# RouteurPV2107d.net
KiCad netlist of a schematic drawn in EAGLE
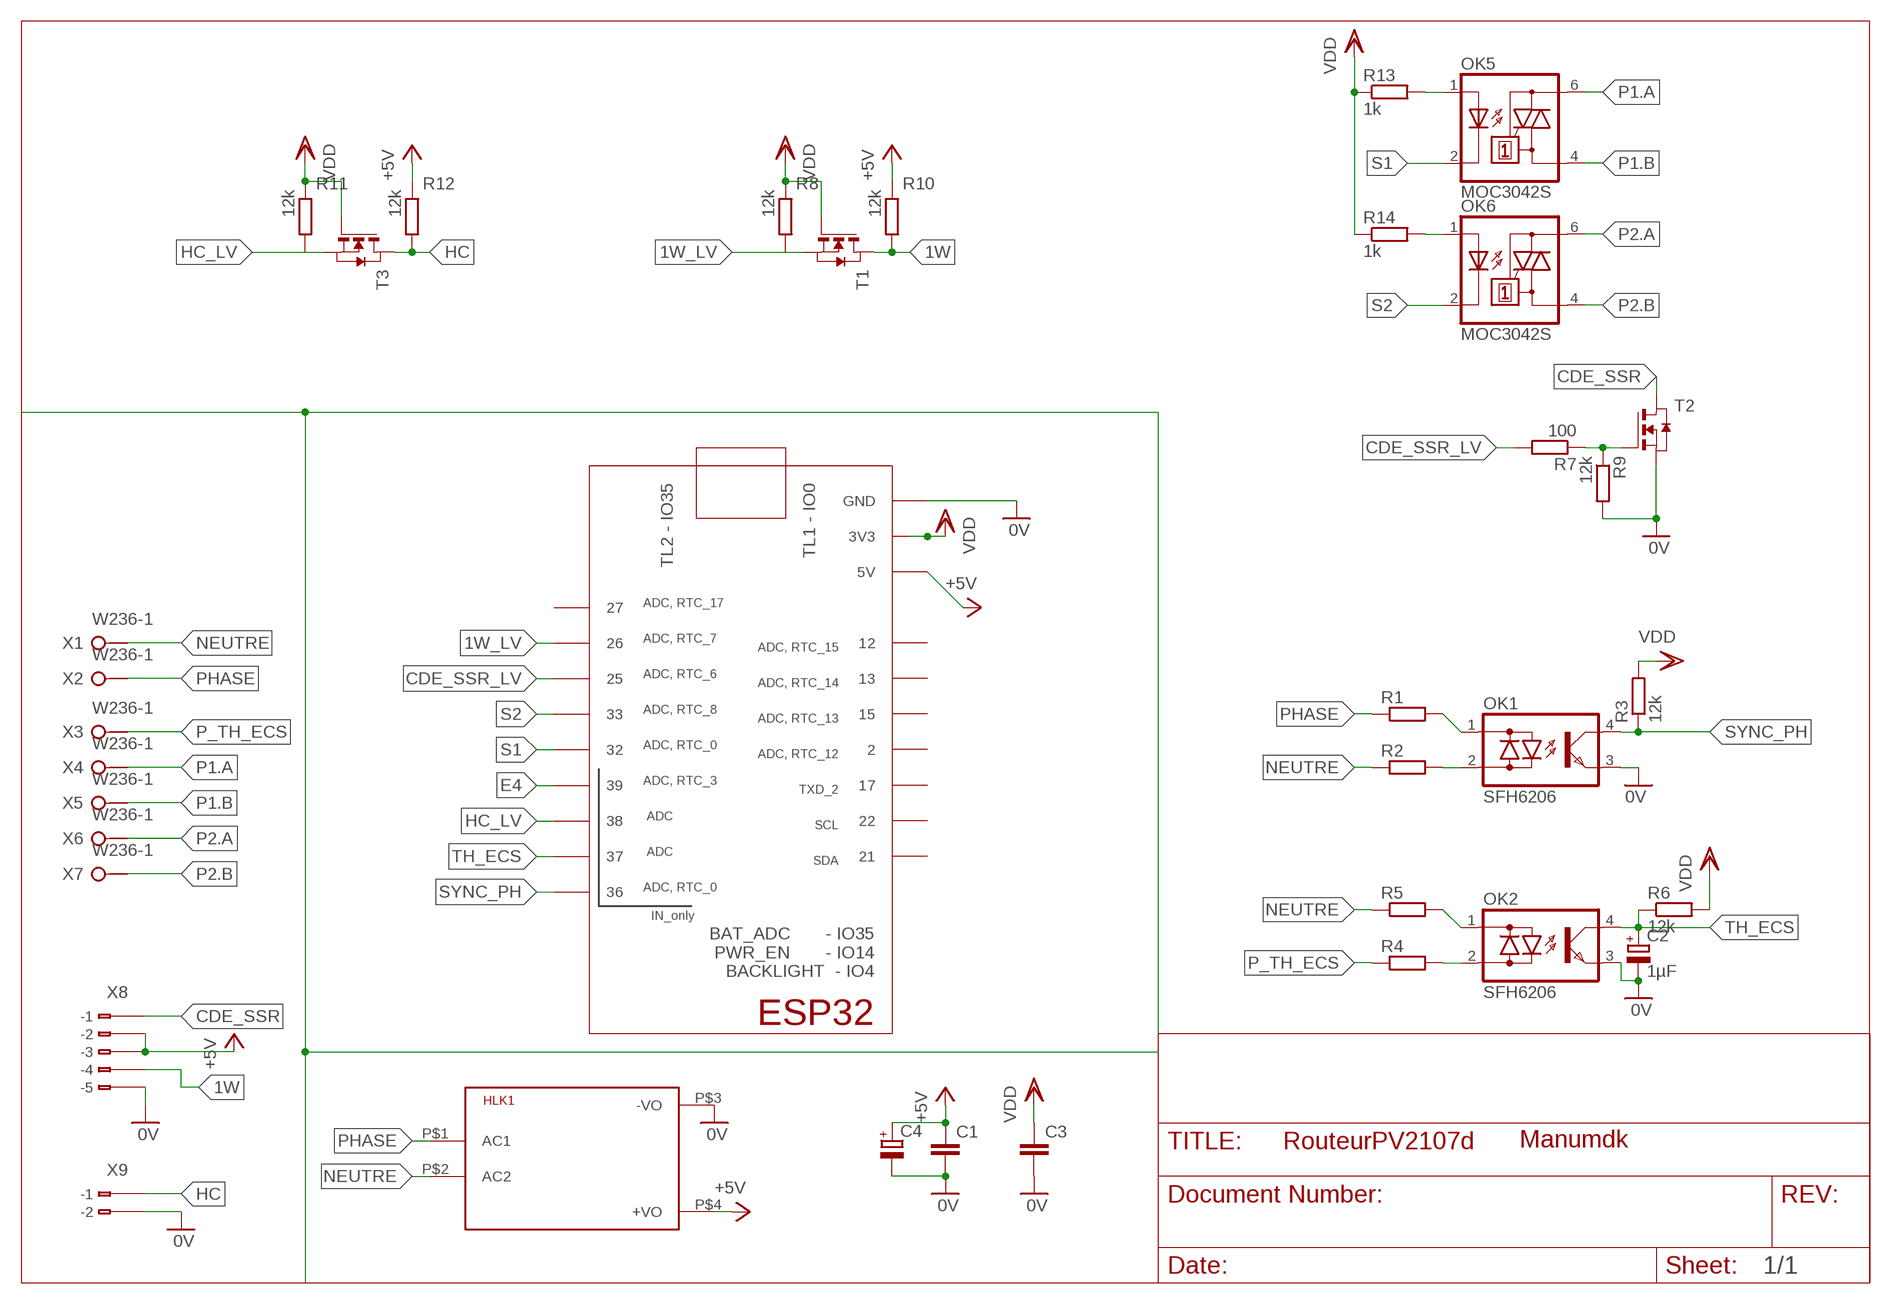
[diagram p0: schematic, sheet 1]

(export (version "E")
  (design (tool "Eeschema 10.0.6"))
  (components
    (comp (ref "C1")
      (value "C-EUC1206")
      (footprint "eagle-import:C1206")
      (libsource (lib "eagle-import") (part "C-EUC1206"))
    )
    (comp (ref "C2")
      (value "1µF")
      (footprint "eagle-import:R_2012-12R")
      (libsource (lib "eagle-import") (part "CPOL-EUR/2012-12R"))
    )
    (comp (ref "C3")
      (value "C-EUC1206")
      (footprint "eagle-import:C1206")
      (libsource (lib "eagle-import") (part "C-EUC1206"))
    )
    (comp (ref "C4")
      (value "CPOL-EUSMCC")
      (footprint "eagle-import:SMC_C")
      (libsource (lib "eagle-import") (part "CPOL-EUSMCC"))
    )
    (comp (ref "HLK1")
      (value "HLK-PM013W")
      (footprint "eagle-import:HLK-PM01")
      (libsource (lib "eagle-import") (part "HLK-PM013W"))
    )
    (comp (ref "IC1")
      (value "TTGO_DISP")
      (footprint "eagle-import:TTGO_DISP_DEFAULT")
      (libsource (lib "eagle-import") (part "TTGO_DISP"))
    )
    (comp (ref "OK1")
      (value "SFH6206")
      (footprint "eagle-import:DIL4-SMD")
      (fields (field (name "MF") "VISHAY/TELEFUNKEN") (field (name "MPN") "SFH6206-3"))
      (libsource (lib "eagle-import") (part "SFH6206"))
    )
    (comp (ref "OK2")
      (value "SFH6206")
      (footprint "eagle-import:DIL4-SMD")
      (fields (field (name "MF") "VISHAY/TELEFUNKEN") (field (name "MPN") "SFH6206-3"))
      (libsource (lib "eagle-import") (part "SFH6206"))
    )
    (comp (ref "OK5")
      (value "MOC3042S")
      (footprint "eagle-import:DIL6-SMD")
      (fields (field (name "MF") "FAIRCHILD SEMICONDUCTOR") (field (name "MPN") "MOC3042SM"))
      (libsource (lib "eagle-import") (part "MOC30S42"))
    )
    (comp (ref "OK6")
      (value "MOC3042S")
      (footprint "eagle-import:DIL6-SMD")
      (fields (field (name "MF") "FAIRCHILD SEMICONDUCTOR") (field (name "MPN") "MOC3042SM"))
      (libsource (lib "eagle-import") (part "MOC30S42"))
    )
    (comp (ref "R1")
      (value "R-EU_R2512")
      (footprint "eagle-import:R2512")
      (libsource (lib "eagle-import") (part "R-EU_R2512"))
    )
    (comp (ref "R2")
      (value "R-EU_R2512")
      (footprint "eagle-import:R2512")
      (libsource (lib "eagle-import") (part "R-EU_R2512"))
    )
    (comp (ref "R3")
      (value "12k")
      (footprint "eagle-import:R1206")
      (libsource (lib "eagle-import") (part "R-EU_R1206"))
    )
    (comp (ref "R4")
      (value "R-EU_R2512")
      (footprint "eagle-import:R2512")
      (libsource (lib "eagle-import") (part "R-EU_R2512"))
    )
    (comp (ref "R5")
      (value "R-EU_R2512")
      (footprint "eagle-import:R2512")
      (libsource (lib "eagle-import") (part "R-EU_R2512"))
    )
    (comp (ref "R6")
      (value "12k")
      (footprint "eagle-import:R1206")
      (libsource (lib "eagle-import") (part "R-EU_R1206"))
    )
    (comp (ref "R7")
      (value "100")
      (footprint "eagle-import:R1206")
      (libsource (lib "eagle-import") (part "R-EU_R1206"))
    )
    (comp (ref "R8")
      (value "12k")
      (footprint "eagle-import:R1206")
      (libsource (lib "eagle-import") (part "R-EU_R1206"))
    )
    (comp (ref "R9")
      (value "12k")
      (footprint "eagle-import:R1206")
      (libsource (lib "eagle-import") (part "R-EU_R1206"))
    )
    (comp (ref "R10")
      (value "12k")
      (footprint "eagle-import:R1206")
      (libsource (lib "eagle-import") (part "R-EU_R1206"))
    )
    (comp (ref "R11")
      (value "12k")
      (footprint "eagle-import:R1206")
      (libsource (lib "eagle-import") (part "R-EU_R1206"))
    )
    (comp (ref "R12")
      (value "12k")
      (footprint "eagle-import:R1206")
      (libsource (lib "eagle-import") (part "R-EU_R1206"))
    )
    (comp (ref "R13")
      (value "1k")
      (footprint "eagle-import:R1206")
      (libsource (lib "eagle-import") (part "R-EU_R1206"))
    )
    (comp (ref "R14")
      (value "1k")
      (footprint "eagle-import:R1206")
      (libsource (lib "eagle-import") (part "R-EU_R1206"))
    )
    (comp (ref "T1")
      (value "NMOSSOT23")
      (footprint "eagle-import:SOT-23")
      (libsource (lib "eagle-import") (part "NMOSSOT23"))
    )
    (comp (ref "T2")
      (value "NMOSSOT23")
      (footprint "eagle-import:SOT-23")
      (libsource (lib "eagle-import") (part "NMOSSOT23"))
    )
    (comp (ref "T3")
      (value "NMOSSOT23")
      (footprint "eagle-import:SOT-23")
      (libsource (lib "eagle-import") (part "NMOSSOT23"))
    )
    (comp (ref "X1")
      (value "W236-1")
      (footprint "eagle-import:W236-1")
      (libsource (lib "eagle-import") (part "W236-1"))
    )
    (comp (ref "X2")
      (value "W236-1")
      (footprint "eagle-import:W236-1")
      (libsource (lib "eagle-import") (part "W236-1"))
    )
    (comp (ref "X3")
      (value "W236-1")
      (footprint "eagle-import:W236-1")
      (libsource (lib "eagle-import") (part "W236-1"))
    )
    (comp (ref "X4")
      (value "W236-1")
      (footprint "eagle-import:W236-1")
      (libsource (lib "eagle-import") (part "W236-1"))
    )
    (comp (ref "X5")
      (value "W236-1")
      (footprint "eagle-import:W236-1")
      (libsource (lib "eagle-import") (part "W236-1"))
    )
    (comp (ref "X6")
      (value "W236-1")
      (footprint "eagle-import:W236-1")
      (libsource (lib "eagle-import") (part "W236-1"))
    )
    (comp (ref "X7")
      (value "W236-1")
      (footprint "eagle-import:W236-1")
      (libsource (lib "eagle-import") (part "W236-1"))
    )
    (comp (ref "X8")
      (value "233-505")
      (footprint "eagle-import:233-505")
      (fields (field (name "MF") "Wago Corporation") (field (name "MPN") "0233-0505"))
      (libsource (lib "eagle-import") (part "233-505"))
    )
    (comp (ref "X9")
      (value "233-102")
      (footprint "eagle-import:233-102")
      (libsource (lib "eagle-import") (part "233-102"))
    )
  )
  (nets
    (net (code "1") (name "+5V") (class "Default")
      (node (ref "C1") (pin "1") (pinfunction "1_1") (pintype "passive"))
      (node (ref "C4") (pin "+") (pinfunction "+_+") (pintype "passive"))
      (node (ref "HLK1") (pin "P$4") (pinfunction "+VO_P$4") (pintype "bidirectional"))
      (node (ref "IC1") (pin "5V") (pinfunction "5V_5V") (pintype "bidirectional"))
      (node (ref "R10") (pin "1") (pinfunction "1_1") (pintype "passive"))
      (node (ref "R12") (pin "1") (pinfunction "1_1") (pintype "passive"))
      (node (ref "X8") (pin "B2") (pinfunction "B-2_B2") (pintype "passive"))
      (node (ref "X8") (pin "B3") (pinfunction "B-3_B3") (pintype "passive"))
    )
    (net (code "2") (name "0V") (class "Default")
      (node (ref "C1") (pin "2") (pinfunction "2_2") (pintype "passive"))
      (node (ref "C2") (pin "-") (pinfunction "-_-") (pintype "passive"))
      (node (ref "C3") (pin "2") (pinfunction "2_2") (pintype "passive"))
      (node (ref "C4") (pin "-") (pinfunction "-_-") (pintype "passive"))
      (node (ref "HLK1") (pin "P$3") (pinfunction "-VO_P$3") (pintype "bidirectional"))
      (node (ref "IC1") (pin "GND_1") (pinfunction "GND_GND_1") (pintype "bidirectional"))
      (node (ref "IC1") (pin "GND_2") (pinfunction "GND_GND_2") (pintype "bidirectional"))
      (node (ref "IC1") (pin "GND_3") (pinfunction "GND_GND_3") (pintype "bidirectional"))
      (node (ref "IC1") (pin "GND_4") (pinfunction "GND_GND_4") (pintype "bidirectional"))
      (node (ref "IC1") (pin "GND_5") (pinfunction "GND_GND_5") (pintype "bidirectional"))
      (node (ref "OK1") (pin "3") (pinfunction "E_3") (pintype "passive"))
      (node (ref "OK2") (pin "3") (pinfunction "E_3") (pintype "passive"))
      (node (ref "R9") (pin "2") (pinfunction "2_2") (pintype "passive"))
      (node (ref "T2") (pin "2") (pinfunction "S_2") (pintype "passive"))
      (node (ref "X8") (pin "B5") (pinfunction "B-5_B5") (pintype "passive"))
      (node (ref "X9") (pin "B2") (pinfunction "B-2_B2") (pintype "passive"))
    )
    (net (code "3") (name "1W") (class "Default")
      (node (ref "R10") (pin "2") (pinfunction "2_2") (pintype "passive"))
      (node (ref "T1") (pin "1") (pinfunction "D_1") (pintype "passive"))
      (node (ref "X8") (pin "B4") (pinfunction "B-4_B4") (pintype "passive"))
    )
    (net (code "4") (name "1W_LV") (class "Default")
      (node (ref "IC1") (pin "26") (pinfunction "26_26") (pintype "bidirectional"))
      (node (ref "R8") (pin "2") (pinfunction "2_2") (pintype "passive"))
      (node (ref "T1") (pin "2") (pinfunction "S_2") (pintype "passive"))
    )
    (net (code "5") (name "CDE_SSR") (class "Default")
      (node (ref "T2") (pin "1") (pinfunction "D_1") (pintype "passive"))
      (node (ref "X8") (pin "B1") (pinfunction "B-1_B1") (pintype "passive"))
    )
    (net (code "6") (name "CDE_SSR_LV") (class "Default")
      (node (ref "IC1") (pin "25") (pinfunction "25_25") (pintype "bidirectional"))
      (node (ref "R7") (pin "2") (pinfunction "2_2") (pintype "passive"))
    )
    (net (code "7") (name "E4") (class "Default")
      (node (ref "IC1") (pin "39") (pinfunction "39_39") (pintype "bidirectional"))
    )
    (net (code "8") (name "HC") (class "Default")
      (node (ref "R12") (pin "2") (pinfunction "2_2") (pintype "passive"))
      (node (ref "T3") (pin "1") (pinfunction "D_1") (pintype "passive"))
      (node (ref "X9") (pin "B1") (pinfunction "B-1_B1") (pintype "passive"))
    )
    (net (code "9") (name "HC_LV") (class "Default")
      (node (ref "IC1") (pin "38") (pinfunction "38_38") (pintype "bidirectional"))
      (node (ref "R11") (pin "2") (pinfunction "2_2") (pintype "passive"))
      (node (ref "T3") (pin "2") (pinfunction "S_2") (pintype "passive"))
    )
    (net (code "10") (name "NEUTRE") (class "Default")
      (node (ref "HLK1") (pin "P$2") (pinfunction "AC2_P$2") (pintype "bidirectional"))
      (node (ref "R2") (pin "1") (pinfunction "1_1") (pintype "passive"))
      (node (ref "R5") (pin "1") (pinfunction "1_1") (pintype "passive"))
      (node (ref "X1") (pin "1") (pinfunction "KL1_1") (pintype "passive"))
    )
    (net (code "11") (name "Net-(OK1-AC1)") (class "Default")
      (node (ref "OK1") (pin "1") (pinfunction "AC1_1") (pintype "passive"))
      (node (ref "R1") (pin "2") (pinfunction "2_2") (pintype "passive"))
    )
    (net (code "12") (name "Net-(OK1-AC2)") (class "Default")
      (node (ref "OK1") (pin "2") (pinfunction "AC2_2") (pintype "passive"))
      (node (ref "R2") (pin "2") (pinfunction "2_2") (pintype "passive"))
    )
    (net (code "13") (name "Net-(OK2-AC1)") (class "Default")
      (node (ref "OK2") (pin "1") (pinfunction "AC1_1") (pintype "passive"))
      (node (ref "R5") (pin "2") (pinfunction "2_2") (pintype "passive"))
    )
    (net (code "14") (name "Net-(OK2-AC2)") (class "Default")
      (node (ref "OK2") (pin "2") (pinfunction "AC2_2") (pintype "passive"))
      (node (ref "R4") (pin "2") (pinfunction "2_2") (pintype "passive"))
    )
    (net (code "15") (name "Net-(OK5-A)") (class "Default")
      (node (ref "OK5") (pin "1") (pinfunction "A_1") (pintype "passive"))
      (node (ref "R13") (pin "2") (pinfunction "2_2") (pintype "passive"))
    )
    (net (code "16") (name "Net-(OK6-A)") (class "Default")
      (node (ref "OK6") (pin "1") (pinfunction "A_1") (pintype "passive"))
      (node (ref "R14") (pin "2") (pinfunction "2_2") (pintype "passive"))
    )
    (net (code "17") (name "Net-(T2-G)") (class "Default")
      (node (ref "R7") (pin "1") (pinfunction "1_1") (pintype "passive"))
      (node (ref "R9") (pin "1") (pinfunction "1_1") (pintype "passive"))
      (node (ref "T2") (pin "3") (pinfunction "G_3") (pintype "passive"))
    )
    (net (code "18") (name "P1.A") (class "Default")
      (node (ref "OK5") (pin "6") (pinfunction "A2_6") (pintype "passive"))
      (node (ref "X4") (pin "1") (pinfunction "KL1_1") (pintype "passive"))
    )
    (net (code "19") (name "P1.B") (class "Default")
      (node (ref "OK5") (pin "4") (pinfunction "A1_4") (pintype "passive"))
      (node (ref "X5") (pin "1") (pinfunction "KL1_1") (pintype "passive"))
    )
    (net (code "20") (name "P2.A") (class "Default")
      (node (ref "OK6") (pin "6") (pinfunction "A2_6") (pintype "passive"))
      (node (ref "X6") (pin "1") (pinfunction "KL1_1") (pintype "passive"))
    )
    (net (code "21") (name "P2.B") (class "Default")
      (node (ref "OK6") (pin "4") (pinfunction "A1_4") (pintype "passive"))
      (node (ref "X7") (pin "1") (pinfunction "KL1_1") (pintype "passive"))
    )
    (net (code "22") (name "PHASE") (class "Default")
      (node (ref "HLK1") (pin "P$1") (pinfunction "AC1_P$1") (pintype "bidirectional"))
      (node (ref "R1") (pin "1") (pinfunction "1_1") (pintype "passive"))
      (node (ref "X2") (pin "1") (pinfunction "KL1_1") (pintype "passive"))
    )
    (net (code "23") (name "P_TH_ECS") (class "Default")
      (node (ref "R4") (pin "1") (pinfunction "1_1") (pintype "passive"))
      (node (ref "X3") (pin "1") (pinfunction "KL1_1") (pintype "passive"))
    )
    (net (code "24") (name "S1") (class "Default")
      (node (ref "IC1") (pin "32") (pinfunction "32_32") (pintype "bidirectional"))
      (node (ref "OK5") (pin "2") (pinfunction "C_2") (pintype "passive"))
    )
    (net (code "25") (name "S2") (class "Default")
      (node (ref "IC1") (pin "33") (pinfunction "33_33") (pintype "bidirectional"))
      (node (ref "OK6") (pin "2") (pinfunction "C_2") (pintype "passive"))
    )
    (net (code "26") (name "SYNC_PH") (class "Default")
      (node (ref "IC1") (pin "36") (pinfunction "36_36") (pintype "bidirectional"))
      (node (ref "OK1") (pin "4") (pinfunction "C_4") (pintype "passive"))
      (node (ref "R3") (pin "1") (pinfunction "1_1") (pintype "passive"))
    )
    (net (code "27") (name "TH_ECS") (class "Default")
      (node (ref "C2") (pin "+") (pinfunction "+_+") (pintype "passive"))
      (node (ref "IC1") (pin "37") (pinfunction "37_37") (pintype "bidirectional"))
      (node (ref "OK2") (pin "4") (pinfunction "C_4") (pintype "passive"))
      (node (ref "R6") (pin "1") (pinfunction "1_1") (pintype "passive"))
    )
    (net (code "28") (name "VDD") (class "Default")
      (node (ref "C3") (pin "1") (pinfunction "1_1") (pintype "passive"))
      (node (ref "IC1") (pin "3V3_1") (pinfunction "3V3_3V3_1") (pintype "bidirectional"))
      (node (ref "IC1") (pin "3V3_2") (pinfunction "3V3_3V3_2") (pintype "bidirectional"))
      (node (ref "R11") (pin "1") (pinfunction "1_1") (pintype "passive"))
      (node (ref "R13") (pin "1") (pinfunction "1_1") (pintype "passive"))
      (node (ref "R14") (pin "1") (pinfunction "1_1") (pintype "passive"))
      (node (ref "R3") (pin "2") (pinfunction "2_2") (pintype "passive"))
      (node (ref "R6") (pin "2") (pinfunction "2_2") (pintype "passive"))
      (node (ref "R8") (pin "1") (pinfunction "1_1") (pintype "passive"))
      (node (ref "T1") (pin "3") (pinfunction "G_3") (pintype "passive"))
      (node (ref "T3") (pin "3") (pinfunction "G_3") (pintype "passive"))
    )
    (net (code "29") (name "unconnected-(IC1-Pad2)") (class "Default")
      (node (ref "IC1") (pin "2") (pinfunction "2_2") (pintype "bidirectional"))
    )
    (net (code "30") (name "unconnected-(IC1-Pad12)") (class "Default")
      (node (ref "IC1") (pin "12") (pinfunction "12_12") (pintype "bidirectional"))
    )
    (net (code "31") (name "unconnected-(IC1-Pad13)") (class "Default")
      (node (ref "IC1") (pin "13") (pinfunction "13_13") (pintype "bidirectional"))
    )
    (net (code "32") (name "unconnected-(IC1-Pad15)") (class "Default")
      (node (ref "IC1") (pin "15") (pinfunction "15_15") (pintype "bidirectional"))
    )
    (net (code "33") (name "unconnected-(IC1-Pad17)") (class "Default")
      (node (ref "IC1") (pin "17") (pinfunction "17_17") (pintype "bidirectional"))
    )
    (net (code "34") (name "unconnected-(IC1-Pad21)") (class "Default")
      (node (ref "IC1") (pin "21") (pinfunction "21_21") (pintype "bidirectional"))
    )
    (net (code "35") (name "unconnected-(IC1-Pad22)") (class "Default")
      (node (ref "IC1") (pin "22") (pinfunction "22_22") (pintype "bidirectional"))
    )
    (net (code "36") (name "unconnected-(IC1-Pad27)") (class "Default")
      (node (ref "IC1") (pin "27") (pinfunction "27_27") (pintype "bidirectional"))
    )
    (net (code "37") (name "unconnected-(X1-KL2-Pad2)") (class "Default")
      (node (ref "X1") (pin "2") (pinfunction "KL2_2") (pintype "passive"))
    )
    (net (code "38") (name "unconnected-(X2-KL2-Pad2)") (class "Default")
      (node (ref "X2") (pin "2") (pinfunction "KL2_2") (pintype "passive"))
    )
    (net (code "39") (name "unconnected-(X3-KL2-Pad2)") (class "Default")
      (node (ref "X3") (pin "2") (pinfunction "KL2_2") (pintype "passive"))
    )
    (net (code "40") (name "unconnected-(X4-KL2-Pad2)") (class "Default")
      (node (ref "X4") (pin "2") (pinfunction "KL2_2") (pintype "passive"))
    )
    (net (code "41") (name "unconnected-(X5-KL2-Pad2)") (class "Default")
      (node (ref "X5") (pin "2") (pinfunction "KL2_2") (pintype "passive"))
    )
    (net (code "42") (name "unconnected-(X6-KL2-Pad2)") (class "Default")
      (node (ref "X6") (pin "2") (pinfunction "KL2_2") (pintype "passive"))
    )
    (net (code "43") (name "unconnected-(X7-KL2-Pad2)") (class "Default")
      (node (ref "X7") (pin "2") (pinfunction "KL2_2") (pintype "passive"))
    )
    (net (code "44") (name "unconnected-(X8--1-PadA1)") (class "Default")
      (node (ref "X8") (pin "A1") (pinfunction "-1_A1") (pintype "passive"))
    )
    (net (code "45") (name "unconnected-(X8--2-PadA2)") (class "Default")
      (node (ref "X8") (pin "A2") (pinfunction "-2_A2") (pintype "passive"))
    )
    (net (code "46") (name "unconnected-(X8--3-PadA3)") (class "Default")
      (node (ref "X8") (pin "A3") (pinfunction "-3_A3") (pintype "passive"))
    )
    (net (code "47") (name "unconnected-(X8--4-PadA4)") (class "Default")
      (node (ref "X8") (pin "A4") (pinfunction "-4_A4") (pintype "passive"))
    )
    (net (code "48") (name "unconnected-(X8--5-PadA5)") (class "Default")
      (node (ref "X8") (pin "A5") (pinfunction "-5_A5") (pintype "passive"))
    )
    (net (code "49") (name "unconnected-(X9--1-PadA1)") (class "Default")
      (node (ref "X9") (pin "A1") (pinfunction "-1_A1") (pintype "passive"))
    )
    (net (code "50") (name "unconnected-(X9--2-PadA2)") (class "Default")
      (node (ref "X9") (pin "A2") (pinfunction "-2_A2") (pintype "passive"))
    )
  )
)
